# PCB-ACMb.net
KiCad netlist of a schematic drawn in EAGLE
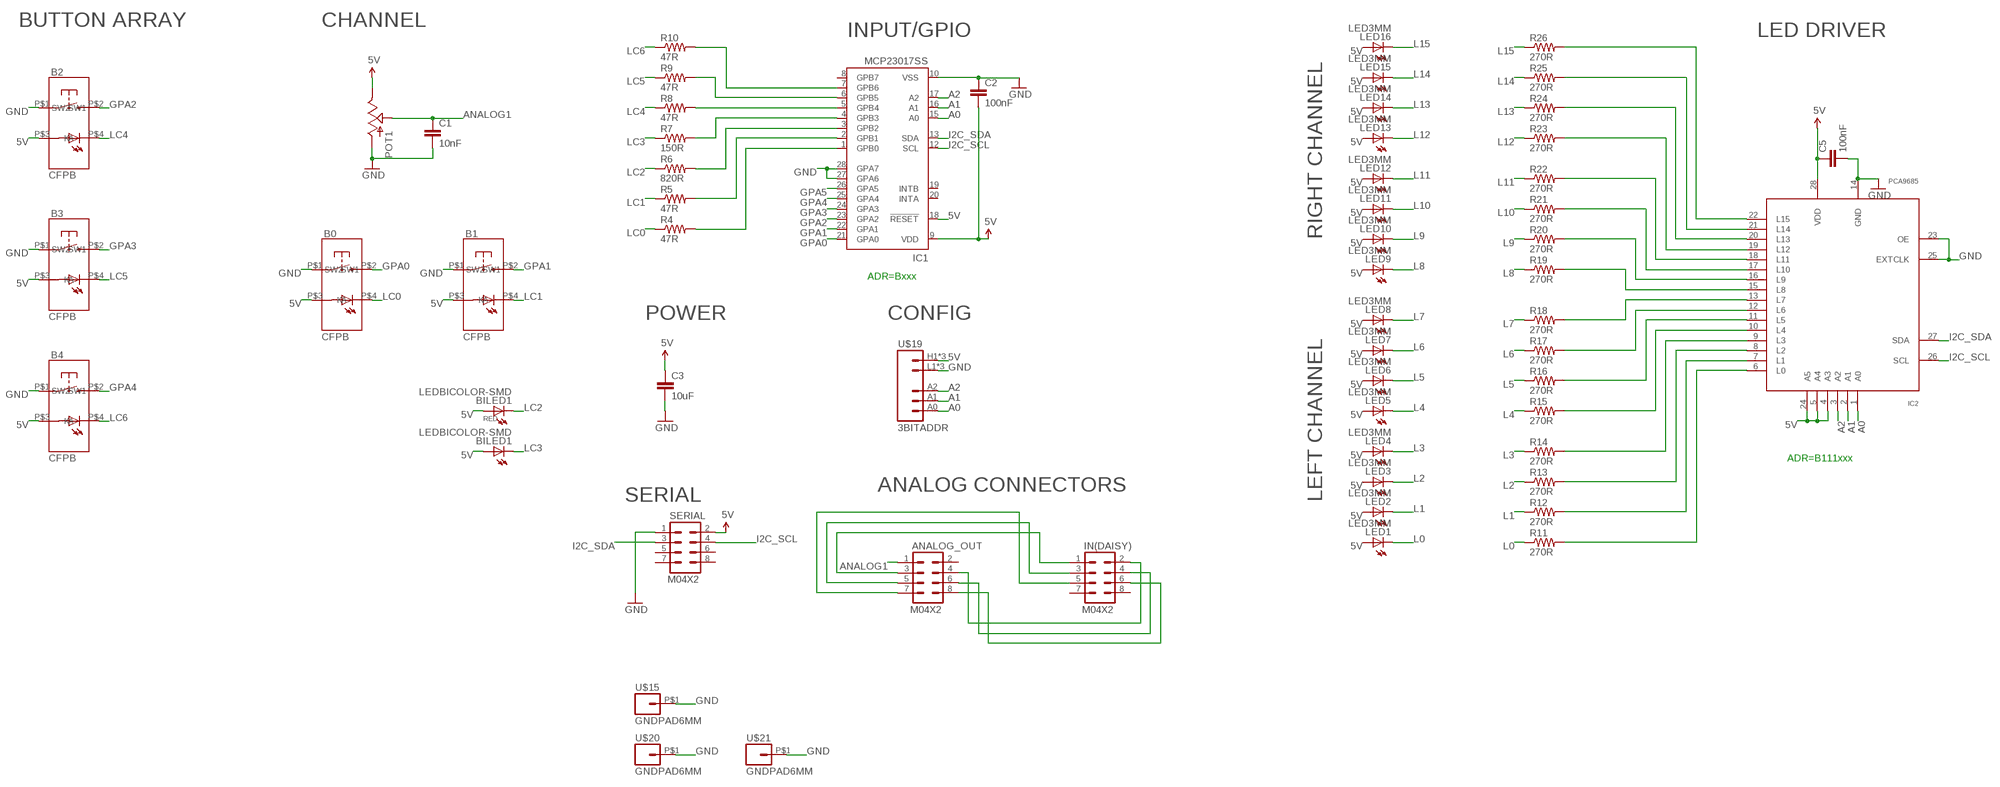
[diagram p0: schematic, sheet 1]

(export (version "E")
  (design (tool "Eeschema 10.0.6"))
  (components
    (comp (ref "ANALOG_OUT")
      (value "M04X2")
      (footprint "eagle-import:2X4")
      (libsource (lib "eagle-import") (part "M04X2"))
    )
    (comp (ref "B0")
      (value "CFPB")
      (footprint "eagle-import:CFPB-6_9MM")
      (libsource (lib "eagle-import") (part "CFPB"))
    )
    (comp (ref "B1")
      (value "CFPB")
      (footprint "eagle-import:CFPB-6_9MM")
      (libsource (lib "eagle-import") (part "CFPB"))
    )
    (comp (ref "B2")
      (value "CFPB")
      (footprint "eagle-import:CFPB-6_9MM")
      (libsource (lib "eagle-import") (part "CFPB"))
    )
    (comp (ref "B3")
      (value "CFPB")
      (footprint "eagle-import:CFPB-6_9MM")
      (libsource (lib "eagle-import") (part "CFPB"))
    )
    (comp (ref "B4")
      (value "CFPB")
      (footprint "eagle-import:CFPB-6_9MM")
      (libsource (lib "eagle-import") (part "CFPB"))
    )
    (comp (ref "BILED1")
      (value "LEDBICOLOR-SMD")
      (footprint "eagle-import:LEDBICOLOR-SMD")
      (libsource (lib "eagle-import") (part "LEDBICOLOR-SMD"))
    )
    (comp (ref "C1")
      (value "10nF")
      (footprint "eagle-import:0603-CAP")
      (libsource (lib "eagle-import") (part "CAP0603-CAP"))
    )
    (comp (ref "C2")
      (value "100nF")
      (footprint "eagle-import:0603-CAP")
      (libsource (lib "eagle-import") (part "CAP0603-CAP"))
    )
    (comp (ref "C3")
      (value "10uF")
      (footprint "eagle-import:0805")
      (libsource (lib "eagle-import") (part "CAP0805"))
    )
    (comp (ref "C5")
      (value "100nF")
      (footprint "eagle-import:0603-CAP")
      (libsource (lib "eagle-import") (part "CAP0603-CAP"))
    )
    (comp (ref "IC1")
      (value "MCP23017SS")
      (footprint "eagle-import:SSOP28")
      (fields
        (field (name "MF") "MICROCHIP")
        (field (name "MPN") "MCP23017-E/SS")
        (field (name "MPN_1") "MCP23017-E/SS")
        (field (name "OC_FARNELL") "1467674")
        (field (name "OC_NEWARK") "31K2960")
      )
      (libsource (lib "eagle-import") (part "MCP23017SS"))
    )
    (comp (ref "IC2")
      (value "PCA9685")
      (footprint "eagle-import:TSSOP28")
      (libsource (lib "eagle-import") (part "PCA9685"))
    )
    (comp (ref "IN(DAISY)")
      (value "M04X2")
      (footprint "eagle-import:2X4")
      (libsource (lib "eagle-import") (part "M04X2"))
    )
    (comp (ref "LED1")
      (value "LED3MM")
      (footprint "eagle-import:LED3MM")
      (libsource (lib "eagle-import") (part "LED3MM"))
    )
    (comp (ref "LED2")
      (value "LED3MM")
      (footprint "eagle-import:LED3MM")
      (libsource (lib "eagle-import") (part "LED3MM"))
    )
    (comp (ref "LED3")
      (value "LED3MM")
      (footprint "eagle-import:LED3MM")
      (libsource (lib "eagle-import") (part "LED3MM"))
    )
    (comp (ref "LED4")
      (value "LED3MM")
      (footprint "eagle-import:LED3MM")
      (libsource (lib "eagle-import") (part "LED3MM"))
    )
    (comp (ref "LED5")
      (value "LED3MM")
      (footprint "eagle-import:LED3MM")
      (libsource (lib "eagle-import") (part "LED3MM"))
    )
    (comp (ref "LED6")
      (value "LED3MM")
      (footprint "eagle-import:LED3MM")
      (libsource (lib "eagle-import") (part "LED3MM"))
    )
    (comp (ref "LED7")
      (value "LED3MM")
      (footprint "eagle-import:LED3MM")
      (libsource (lib "eagle-import") (part "LED3MM"))
    )
    (comp (ref "LED8")
      (value "LED3MM")
      (footprint "eagle-import:LED3MM")
      (libsource (lib "eagle-import") (part "LED3MM"))
    )
    (comp (ref "LED9")
      (value "LED3MM")
      (footprint "eagle-import:LED3MM")
      (libsource (lib "eagle-import") (part "LED3MM"))
    )
    (comp (ref "LED10")
      (value "LED3MM")
      (footprint "eagle-import:LED3MM")
      (libsource (lib "eagle-import") (part "LED3MM"))
    )
    (comp (ref "LED11")
      (value "LED3MM")
      (footprint "eagle-import:LED3MM")
      (libsource (lib "eagle-import") (part "LED3MM"))
    )
    (comp (ref "LED12")
      (value "LED3MM")
      (footprint "eagle-import:LED3MM")
      (libsource (lib "eagle-import") (part "LED3MM"))
    )
    (comp (ref "LED13")
      (value "LED3MM")
      (footprint "eagle-import:LED3MM")
      (libsource (lib "eagle-import") (part "LED3MM"))
    )
    (comp (ref "LED14")
      (value "LED3MM")
      (footprint "eagle-import:LED3MM")
      (libsource (lib "eagle-import") (part "LED3MM"))
    )
    (comp (ref "LED15")
      (value "LED3MM")
      (footprint "eagle-import:LED3MM")
      (libsource (lib "eagle-import") (part "LED3MM"))
    )
    (comp (ref "LED16")
      (value "LED3MM")
      (footprint "eagle-import:LED3MM")
      (libsource (lib "eagle-import") (part "LED3MM"))
    )
    (comp (ref "POT1")
      (value "POT")
      (footprint "eagle-import:ALPS_POT")
      (libsource (lib "eagle-import") (part "POT"))
    )
    (comp (ref "R4")
      (value "47R")
      (footprint "eagle-import:0603-RES")
      (libsource (lib "eagle-import") (part "RESISTOR0603-RES"))
    )
    (comp (ref "R5")
      (value "47R")
      (footprint "eagle-import:0603-RES")
      (libsource (lib "eagle-import") (part "RESISTOR0603-RES"))
    )
    (comp (ref "R6")
      (value "820R")
      (footprint "eagle-import:0603-RES")
      (libsource (lib "eagle-import") (part "RESISTOR0603-RES"))
    )
    (comp (ref "R7")
      (value "150R")
      (footprint "eagle-import:0603-RES")
      (libsource (lib "eagle-import") (part "RESISTOR0603-RES"))
    )
    (comp (ref "R8")
      (value "47R")
      (footprint "eagle-import:0603-RES")
      (libsource (lib "eagle-import") (part "RESISTOR0603-RES"))
    )
    (comp (ref "R9")
      (value "47R")
      (footprint "eagle-import:0603-RES")
      (libsource (lib "eagle-import") (part "RESISTOR0603-RES"))
    )
    (comp (ref "R10")
      (value "47R")
      (footprint "eagle-import:0603-RES")
      (libsource (lib "eagle-import") (part "RESISTOR0603-RES"))
    )
    (comp (ref "R11")
      (value "270R")
      (footprint "eagle-import:0603-RES")
      (libsource (lib "eagle-import") (part "RESISTOR0603-RES"))
    )
    (comp (ref "R12")
      (value "270R")
      (footprint "eagle-import:0603-RES")
      (libsource (lib "eagle-import") (part "RESISTOR0603-RES"))
    )
    (comp (ref "R13")
      (value "270R")
      (footprint "eagle-import:0603-RES")
      (libsource (lib "eagle-import") (part "RESISTOR0603-RES"))
    )
    (comp (ref "R14")
      (value "270R")
      (footprint "eagle-import:0603-RES")
      (libsource (lib "eagle-import") (part "RESISTOR0603-RES"))
    )
    (comp (ref "R15")
      (value "270R")
      (footprint "eagle-import:0603-RES")
      (libsource (lib "eagle-import") (part "RESISTOR0603-RES"))
    )
    (comp (ref "R16")
      (value "270R")
      (footprint "eagle-import:0603-RES")
      (libsource (lib "eagle-import") (part "RESISTOR0603-RES"))
    )
    (comp (ref "R17")
      (value "270R")
      (footprint "eagle-import:0603-RES")
      (libsource (lib "eagle-import") (part "RESISTOR0603-RES"))
    )
    (comp (ref "R18")
      (value "270R")
      (footprint "eagle-import:0603-RES")
      (libsource (lib "eagle-import") (part "RESISTOR0603-RES"))
    )
    (comp (ref "R19")
      (value "270R")
      (footprint "eagle-import:0603-RES")
      (libsource (lib "eagle-import") (part "RESISTOR0603-RES"))
    )
    (comp (ref "R20")
      (value "270R")
      (footprint "eagle-import:0603-RES")
      (libsource (lib "eagle-import") (part "RESISTOR0603-RES"))
    )
    (comp (ref "R21")
      (value "270R")
      (footprint "eagle-import:0603-RES")
      (libsource (lib "eagle-import") (part "RESISTOR0603-RES"))
    )
    (comp (ref "R22")
      (value "270R")
      (footprint "eagle-import:0603-RES")
      (libsource (lib "eagle-import") (part "RESISTOR0603-RES"))
    )
    (comp (ref "R23")
      (value "270R")
      (footprint "eagle-import:0603-RES")
      (libsource (lib "eagle-import") (part "RESISTOR0603-RES"))
    )
    (comp (ref "R24")
      (value "270R")
      (footprint "eagle-import:0603-RES")
      (libsource (lib "eagle-import") (part "RESISTOR0603-RES"))
    )
    (comp (ref "R25")
      (value "270R")
      (footprint "eagle-import:0603-RES")
      (libsource (lib "eagle-import") (part "RESISTOR0603-RES"))
    )
    (comp (ref "R26")
      (value "270R")
      (footprint "eagle-import:0603-RES")
      (libsource (lib "eagle-import") (part "RESISTOR0603-RES"))
    )
    (comp (ref "SERIAL")
      (value "M04X2")
      (footprint "eagle-import:2X4")
      (libsource (lib "eagle-import") (part "M04X2"))
    )
    (comp (ref "U$15")
      (value "GNDPAD6MM")
      (footprint "eagle-import:3.2MMPAD6MM")
      (libsource (lib "eagle-import") (part "GNDPAD6MM"))
    )
    (comp (ref "U$19")
      (value "3BITADDR")
      (footprint "eagle-import:3BITADDR")
      (libsource (lib "eagle-import") (part "3BITADDR"))
    )
    (comp (ref "U$20")
      (value "GNDPAD6MM")
      (footprint "eagle-import:3.2MMPAD6MM")
      (libsource (lib "eagle-import") (part "GNDPAD6MM"))
    )
    (comp (ref "U$21")
      (value "GNDPAD6MM")
      (footprint "eagle-import:3.2MMPAD6MM")
      (libsource (lib "eagle-import") (part "GNDPAD6MM"))
    )
  )
  (nets
    (net (code "1") (name "/A0") (class "Default")
      (node (ref "IC1") (pin "15") (pinfunction "A0_15") (pintype "input"))
      (node (ref "IC2") (pin "1") (pinfunction "A0_1") (pintype "input"))
      (node (ref "U$19") (pin "A0") (pinfunction "A0_A0") (pintype "passive"))
    )
    (net (code "2") (name "/A1") (class "Default")
      (node (ref "IC1") (pin "16") (pinfunction "A1_16") (pintype "input"))
      (node (ref "IC2") (pin "2") (pinfunction "A1_2") (pintype "input"))
      (node (ref "U$19") (pin "A1") (pinfunction "A1_A1") (pintype "passive"))
    )
    (net (code "3") (name "/A2") (class "Default")
      (node (ref "IC1") (pin "17") (pinfunction "A2_17") (pintype "input"))
      (node (ref "IC2") (pin "3") (pinfunction "A2_3") (pintype "input"))
      (node (ref "U$19") (pin "A2") (pinfunction "A2_A2") (pintype "passive"))
    )
    (net (code "4") (name "/ANALOG1") (class "Default")
      (node (ref "ANALOG_OUT") (pin "1") (pinfunction "1_1") (pintype "passive"))
      (node (ref "C1") (pin "1") (pinfunction "1_1") (pintype "passive"))
      (node (ref "POT1") (pin "P$2") (pinfunction "S_P$2") (pintype "passive"))
    )
    (net (code "5") (name "/GPA0") (class "Default")
      (node (ref "B0") (pin "P$2") (pinfunction "SW2_P$2") (pintype "bidirectional"))
      (node (ref "IC1") (pin "21") (pinfunction "GPA0_21") (pintype "bidirectional"))
    )
    (net (code "6") (name "/GPA1") (class "Default")
      (node (ref "B1") (pin "P$2") (pinfunction "SW2_P$2") (pintype "bidirectional"))
      (node (ref "IC1") (pin "22") (pinfunction "GPA1_22") (pintype "bidirectional"))
    )
    (net (code "7") (name "/GPA2") (class "Default")
      (node (ref "B2") (pin "P$2") (pinfunction "SW2_P$2") (pintype "bidirectional"))
      (node (ref "IC1") (pin "23") (pinfunction "GPA2_23") (pintype "bidirectional"))
    )
    (net (code "8") (name "/GPA3") (class "Default")
      (node (ref "B3") (pin "P$2") (pinfunction "SW2_P$2") (pintype "bidirectional"))
      (node (ref "IC1") (pin "24") (pinfunction "GPA3_24") (pintype "bidirectional"))
    )
    (net (code "9") (name "/GPA4") (class "Default")
      (node (ref "B4") (pin "P$2") (pinfunction "SW2_P$2") (pintype "bidirectional"))
      (node (ref "IC1") (pin "25") (pinfunction "GPA4_25") (pintype "bidirectional"))
    )
    (net (code "10") (name "/GPA5") (class "Default")
      (node (ref "IC1") (pin "26") (pinfunction "GPA5_26") (pintype "bidirectional"))
    )
    (net (code "11") (name "/I2C_SCL") (class "Default")
      (node (ref "IC1") (pin "12") (pinfunction "SCL_12") (pintype "input"))
      (node (ref "IC2") (pin "26") (pinfunction "SCL_26") (pintype "input"))
      (node (ref "SERIAL") (pin "4") (pinfunction "4_4") (pintype "passive"))
    )
    (net (code "12") (name "/I2C_SDA") (class "Default")
      (node (ref "IC1") (pin "13") (pinfunction "SDA_13") (pintype "bidirectional"))
      (node (ref "IC2") (pin "27") (pinfunction "SDA_27") (pintype "input"))
      (node (ref "SERIAL") (pin "3") (pinfunction "3_3") (pintype "passive"))
    )
    (net (code "13") (name "/L0") (class "Default")
      (node (ref "LED1") (pin "K") (pinfunction "C_K") (pintype "passive"))
      (node (ref "R11") (pin "1") (pinfunction "1_1") (pintype "passive"))
    )
    (net (code "14") (name "/L1") (class "Default")
      (node (ref "LED2") (pin "K") (pinfunction "C_K") (pintype "passive"))
      (node (ref "R12") (pin "1") (pinfunction "1_1") (pintype "passive"))
    )
    (net (code "15") (name "/L2") (class "Default")
      (node (ref "LED3") (pin "K") (pinfunction "C_K") (pintype "passive"))
      (node (ref "R13") (pin "1") (pinfunction "1_1") (pintype "passive"))
    )
    (net (code "16") (name "/L3") (class "Default")
      (node (ref "LED4") (pin "K") (pinfunction "C_K") (pintype "passive"))
      (node (ref "R14") (pin "1") (pinfunction "1_1") (pintype "passive"))
    )
    (net (code "17") (name "/L4") (class "Default")
      (node (ref "LED5") (pin "K") (pinfunction "C_K") (pintype "passive"))
      (node (ref "R15") (pin "1") (pinfunction "1_1") (pintype "passive"))
    )
    (net (code "18") (name "/L5") (class "Default")
      (node (ref "LED6") (pin "K") (pinfunction "C_K") (pintype "passive"))
      (node (ref "R16") (pin "1") (pinfunction "1_1") (pintype "passive"))
    )
    (net (code "19") (name "/L6") (class "Default")
      (node (ref "LED7") (pin "K") (pinfunction "C_K") (pintype "passive"))
      (node (ref "R17") (pin "1") (pinfunction "1_1") (pintype "passive"))
    )
    (net (code "20") (name "/L7") (class "Default")
      (node (ref "LED8") (pin "K") (pinfunction "C_K") (pintype "passive"))
      (node (ref "R18") (pin "1") (pinfunction "1_1") (pintype "passive"))
    )
    (net (code "21") (name "/L8") (class "Default")
      (node (ref "LED9") (pin "K") (pinfunction "C_K") (pintype "passive"))
      (node (ref "R19") (pin "1") (pinfunction "1_1") (pintype "passive"))
    )
    (net (code "22") (name "/L9") (class "Default")
      (node (ref "LED10") (pin "K") (pinfunction "C_K") (pintype "passive"))
      (node (ref "R20") (pin "1") (pinfunction "1_1") (pintype "passive"))
    )
    (net (code "23") (name "/L10") (class "Default")
      (node (ref "LED11") (pin "K") (pinfunction "C_K") (pintype "passive"))
      (node (ref "R21") (pin "1") (pinfunction "1_1") (pintype "passive"))
    )
    (net (code "24") (name "/L11") (class "Default")
      (node (ref "LED12") (pin "K") (pinfunction "C_K") (pintype "passive"))
      (node (ref "R22") (pin "1") (pinfunction "1_1") (pintype "passive"))
    )
    (net (code "25") (name "/L12") (class "Default")
      (node (ref "LED13") (pin "K") (pinfunction "C_K") (pintype "passive"))
      (node (ref "R23") (pin "1") (pinfunction "1_1") (pintype "passive"))
    )
    (net (code "26") (name "/L13") (class "Default")
      (node (ref "LED14") (pin "K") (pinfunction "C_K") (pintype "passive"))
      (node (ref "R24") (pin "1") (pinfunction "1_1") (pintype "passive"))
    )
    (net (code "27") (name "/L14") (class "Default")
      (node (ref "LED15") (pin "K") (pinfunction "C_K") (pintype "passive"))
      (node (ref "R25") (pin "1") (pinfunction "1_1") (pintype "passive"))
    )
    (net (code "28") (name "/L15") (class "Default")
      (node (ref "LED16") (pin "K") (pinfunction "C_K") (pintype "passive"))
      (node (ref "R26") (pin "1") (pinfunction "1_1") (pintype "passive"))
    )
    (net (code "29") (name "/LC0") (class "Default")
      (node (ref "B0") (pin "P$4") (pinfunction "K_P$4") (pintype "bidirectional"))
      (node (ref "R4") (pin "1") (pinfunction "1_1") (pintype "passive"))
    )
    (net (code "30") (name "/LC1") (class "Default")
      (node (ref "B1") (pin "P$4") (pinfunction "K_P$4") (pintype "bidirectional"))
      (node (ref "R5") (pin "1") (pinfunction "1_1") (pintype "passive"))
    )
    (net (code "31") (name "/LC2") (class "Default")
      (node (ref "BILED1") (pin "P$2") (pinfunction "C_P$2") (pintype "passive"))
      (node (ref "R6") (pin "1") (pinfunction "1_1") (pintype "passive"))
    )
    (net (code "32") (name "/LC3") (class "Default")
      (node (ref "BILED1") (pin "P$4") (pinfunction "C1_P$4") (pintype "passive"))
      (node (ref "R7") (pin "1") (pinfunction "1_1") (pintype "passive"))
    )
    (net (code "33") (name "/LC4") (class "Default")
      (node (ref "B2") (pin "P$4") (pinfunction "K_P$4") (pintype "bidirectional"))
      (node (ref "R8") (pin "1") (pinfunction "1_1") (pintype "passive"))
    )
    (net (code "34") (name "/LC5") (class "Default")
      (node (ref "B3") (pin "P$4") (pinfunction "K_P$4") (pintype "bidirectional"))
      (node (ref "R9") (pin "1") (pinfunction "1_1") (pintype "passive"))
    )
    (net (code "35") (name "/LC6") (class "Default")
      (node (ref "B4") (pin "P$4") (pinfunction "K_P$4") (pintype "bidirectional"))
      (node (ref "R10") (pin "1") (pinfunction "1_1") (pintype "passive"))
    )
    (net (code "36") (name "5V") (class "Default")
      (node (ref "B0") (pin "P$3") (pinfunction "A_P$3") (pintype "bidirectional"))
      (node (ref "B1") (pin "P$3") (pinfunction "A_P$3") (pintype "bidirectional"))
      (node (ref "B2") (pin "P$3") (pinfunction "A_P$3") (pintype "bidirectional"))
      (node (ref "B3") (pin "P$3") (pinfunction "A_P$3") (pintype "bidirectional"))
      (node (ref "B4") (pin "P$3") (pinfunction "A_P$3") (pintype "bidirectional"))
      (node (ref "BILED1") (pin "P$1") (pinfunction "A_P$1") (pintype "passive"))
      (node (ref "BILED1") (pin "P$3") (pinfunction "A1_P$3") (pintype "passive"))
      (node (ref "C2") (pin "2") (pinfunction "2_2") (pintype "passive"))
      (node (ref "C3") (pin "1") (pinfunction "1_1") (pintype "passive"))
      (node (ref "C5") (pin "1") (pinfunction "1_1") (pintype "passive"))
      (node (ref "IC1") (pin "18") (pinfunction "~{RESET}_18") (pintype "input"))
      (node (ref "IC1") (pin "9") (pinfunction "VDD_9") (pintype "power_in"))
      (node (ref "IC2") (pin "24") (pinfunction "A5_24") (pintype "input"))
      (node (ref "IC2") (pin "28") (pinfunction "VDD_28") (pintype "power_in"))
      (node (ref "IC2") (pin "4") (pinfunction "A3_4") (pintype "input"))
      (node (ref "IC2") (pin "5") (pinfunction "A4_5") (pintype "input"))
      (node (ref "LED1") (pin "A") (pinfunction "A_A") (pintype "passive"))
      (node (ref "LED10") (pin "A") (pinfunction "A_A") (pintype "passive"))
      (node (ref "LED11") (pin "A") (pinfunction "A_A") (pintype "passive"))
      (node (ref "LED12") (pin "A") (pinfunction "A_A") (pintype "passive"))
      (node (ref "LED13") (pin "A") (pinfunction "A_A") (pintype "passive"))
      (node (ref "LED14") (pin "A") (pinfunction "A_A") (pintype "passive"))
      (node (ref "LED15") (pin "A") (pinfunction "A_A") (pintype "passive"))
      (node (ref "LED16") (pin "A") (pinfunction "A_A") (pintype "passive"))
      (node (ref "LED2") (pin "A") (pinfunction "A_A") (pintype "passive"))
      (node (ref "LED3") (pin "A") (pinfunction "A_A") (pintype "passive"))
      (node (ref "LED4") (pin "A") (pinfunction "A_A") (pintype "passive"))
      (node (ref "LED5") (pin "A") (pinfunction "A_A") (pintype "passive"))
      (node (ref "LED6") (pin "A") (pinfunction "A_A") (pintype "passive"))
      (node (ref "LED7") (pin "A") (pinfunction "A_A") (pintype "passive"))
      (node (ref "LED8") (pin "A") (pinfunction "A_A") (pintype "passive"))
      (node (ref "LED9") (pin "A") (pinfunction "A_A") (pintype "passive"))
      (node (ref "POT1") (pin "P$1") (pinfunction "E_P$1") (pintype "passive"))
      (node (ref "SERIAL") (pin "2") (pinfunction "2_2") (pintype "passive"))
      (node (ref "U$19") (pin "H1") (pinfunction "VCC_H1") (pintype "passive"))
      (node (ref "U$19") (pin "H2") (pinfunction "VCC_H2") (pintype "passive"))
      (node (ref "U$19") (pin "H3") (pinfunction "VCC_H3") (pintype "passive"))
    )
    (net (code "37") (name "GND") (class "Default")
      (node (ref "B0") (pin "P$1") (pinfunction "SW1_P$1") (pintype "bidirectional"))
      (node (ref "B1") (pin "P$1") (pinfunction "SW1_P$1") (pintype "bidirectional"))
      (node (ref "B2") (pin "P$1") (pinfunction "SW1_P$1") (pintype "bidirectional"))
      (node (ref "B3") (pin "P$1") (pinfunction "SW1_P$1") (pintype "bidirectional"))
      (node (ref "B4") (pin "P$1") (pinfunction "SW1_P$1") (pintype "bidirectional"))
      (node (ref "C1") (pin "2") (pinfunction "2_2") (pintype "passive"))
      (node (ref "C2") (pin "1") (pinfunction "1_1") (pintype "passive"))
      (node (ref "C3") (pin "2") (pinfunction "2_2") (pintype "passive"))
      (node (ref "C5") (pin "2") (pinfunction "2_2") (pintype "passive"))
      (node (ref "IC1") (pin "10") (pinfunction "VSS_10") (pintype "power_in"))
      (node (ref "IC1") (pin "27") (pinfunction "GPA6_27") (pintype "bidirectional"))
      (node (ref "IC1") (pin "28") (pinfunction "GPA7_28") (pintype "bidirectional"))
      (node (ref "IC2") (pin "14") (pinfunction "GND_14") (pintype "power_in"))
      (node (ref "IC2") (pin "23") (pinfunction "OE_23") (pintype "input"))
      (node (ref "IC2") (pin "25") (pinfunction "EXTCLK_25") (pintype "input"))
      (node (ref "POT1") (pin "P$3") (pinfunction "A_P$3") (pintype "passive"))
      (node (ref "SERIAL") (pin "1") (pinfunction "1_1") (pintype "passive"))
      (node (ref "U$15") (pin "P$1") (pinfunction "1_P$1") (pintype "passive"))
      (node (ref "U$19") (pin "L1") (pinfunction "GND_L1") (pintype "passive"))
      (node (ref "U$19") (pin "L2") (pinfunction "GND_L2") (pintype "passive"))
      (node (ref "U$19") (pin "L3") (pinfunction "GND_L3") (pintype "passive"))
      (node (ref "U$20") (pin "P$1") (pinfunction "1_P$1") (pintype "passive"))
      (node (ref "U$21") (pin "P$1") (pinfunction "1_P$1") (pintype "passive"))
    )
    (net (code "38") (name "Net-(ANALOG_OUT-Pad3)") (class "Default")
      (node (ref "ANALOG_OUT") (pin "3") (pinfunction "3_3") (pintype "passive"))
      (node (ref "IN(DAISY)") (pin "1") (pinfunction "1_1") (pintype "passive"))
    )
    (net (code "39") (name "Net-(ANALOG_OUT-Pad4)") (class "Default")
      (node (ref "ANALOG_OUT") (pin "4") (pinfunction "4_4") (pintype "passive"))
      (node (ref "IN(DAISY)") (pin "2") (pinfunction "2_2") (pintype "passive"))
    )
    (net (code "40") (name "Net-(ANALOG_OUT-Pad5)") (class "Default")
      (node (ref "ANALOG_OUT") (pin "5") (pinfunction "5_5") (pintype "passive"))
      (node (ref "IN(DAISY)") (pin "3") (pinfunction "3_3") (pintype "passive"))
    )
    (net (code "41") (name "Net-(ANALOG_OUT-Pad6)") (class "Default")
      (node (ref "ANALOG_OUT") (pin "6") (pinfunction "6_6") (pintype "passive"))
      (node (ref "IN(DAISY)") (pin "4") (pinfunction "4_4") (pintype "passive"))
    )
    (net (code "42") (name "Net-(ANALOG_OUT-Pad7)") (class "Default")
      (node (ref "ANALOG_OUT") (pin "7") (pinfunction "7_7") (pintype "passive"))
      (node (ref "IN(DAISY)") (pin "5") (pinfunction "5_5") (pintype "passive"))
    )
    (net (code "43") (name "Net-(ANALOG_OUT-Pad8)") (class "Default")
      (node (ref "ANALOG_OUT") (pin "8") (pinfunction "8_8") (pintype "passive"))
      (node (ref "IN(DAISY)") (pin "6") (pinfunction "6_6") (pintype "passive"))
    )
    (net (code "44") (name "Net-(IC1-GPB0)") (class "Default")
      (node (ref "IC1") (pin "1") (pinfunction "GPB0_1") (pintype "bidirectional"))
      (node (ref "R4") (pin "2") (pinfunction "2_2") (pintype "passive"))
    )
    (net (code "45") (name "Net-(IC1-GPB1)") (class "Default")
      (node (ref "IC1") (pin "2") (pinfunction "GPB1_2") (pintype "bidirectional"))
      (node (ref "R5") (pin "2") (pinfunction "2_2") (pintype "passive"))
    )
    (net (code "46") (name "Net-(IC1-GPB2)") (class "Default")
      (node (ref "IC1") (pin "3") (pinfunction "GPB2_3") (pintype "bidirectional"))
      (node (ref "R6") (pin "2") (pinfunction "2_2") (pintype "passive"))
    )
    (net (code "47") (name "Net-(IC1-GPB3)") (class "Default")
      (node (ref "IC1") (pin "4") (pinfunction "GPB3_4") (pintype "bidirectional"))
      (node (ref "R7") (pin "2") (pinfunction "2_2") (pintype "passive"))
    )
    (net (code "48") (name "Net-(IC1-GPB4)") (class "Default")
      (node (ref "IC1") (pin "5") (pinfunction "GPB4_5") (pintype "bidirectional"))
      (node (ref "R8") (pin "2") (pinfunction "2_2") (pintype "passive"))
    )
    (net (code "49") (name "Net-(IC1-GPB5)") (class "Default")
      (node (ref "IC1") (pin "6") (pinfunction "GPB5_6") (pintype "bidirectional"))
      (node (ref "R9") (pin "2") (pinfunction "2_2") (pintype "passive"))
    )
    (net (code "50") (name "Net-(IC1-GPB6)") (class "Default")
      (node (ref "IC1") (pin "7") (pinfunction "GPB6_7") (pintype "bidirectional"))
      (node (ref "R10") (pin "2") (pinfunction "2_2") (pintype "passive"))
    )
    (net (code "51") (name "Net-(IC2-L0)") (class "Default")
      (node (ref "IC2") (pin "6") (pinfunction "L0_6") (pintype "output"))
      (node (ref "R11") (pin "2") (pinfunction "2_2") (pintype "passive"))
    )
    (net (code "52") (name "Net-(IC2-L1)") (class "Default")
      (node (ref "IC2") (pin "7") (pinfunction "L1_7") (pintype "output"))
      (node (ref "R12") (pin "2") (pinfunction "2_2") (pintype "passive"))
    )
    (net (code "53") (name "Net-(IC2-L2)") (class "Default")
      (node (ref "IC2") (pin "8") (pinfunction "L2_8") (pintype "output"))
      (node (ref "R13") (pin "2") (pinfunction "2_2") (pintype "passive"))
    )
    (net (code "54") (name "Net-(IC2-L3)") (class "Default")
      (node (ref "IC2") (pin "9") (pinfunction "L3_9") (pintype "output"))
      (node (ref "R14") (pin "2") (pinfunction "2_2") (pintype "passive"))
    )
    (net (code "55") (name "Net-(IC2-L4)") (class "Default")
      (node (ref "IC2") (pin "10") (pinfunction "L4_10") (pintype "output"))
      (node (ref "R15") (pin "2") (pinfunction "2_2") (pintype "passive"))
    )
    (net (code "56") (name "Net-(IC2-L5)") (class "Default")
      (node (ref "IC2") (pin "11") (pinfunction "L5_11") (pintype "output"))
      (node (ref "R16") (pin "2") (pinfunction "2_2") (pintype "passive"))
    )
    (net (code "57") (name "Net-(IC2-L6)") (class "Default")
      (node (ref "IC2") (pin "12") (pinfunction "L6_12") (pintype "output"))
      (node (ref "R17") (pin "2") (pinfunction "2_2") (pintype "passive"))
    )
    (net (code "58") (name "Net-(IC2-L7)") (class "Default")
      (node (ref "IC2") (pin "13") (pinfunction "L7_13") (pintype "output"))
      (node (ref "R18") (pin "2") (pinfunction "2_2") (pintype "passive"))
    )
    (net (code "59") (name "Net-(IC2-L8)") (class "Default")
      (node (ref "IC2") (pin "15") (pinfunction "L8_15") (pintype "output"))
      (node (ref "R19") (pin "2") (pinfunction "2_2") (pintype "passive"))
    )
    (net (code "60") (name "Net-(IC2-L9)") (class "Default")
      (node (ref "IC2") (pin "16") (pinfunction "L9_16") (pintype "output"))
      (node (ref "R20") (pin "2") (pinfunction "2_2") (pintype "passive"))
    )
    (net (code "61") (name "Net-(IC2-L10)") (class "Default")
      (node (ref "IC2") (pin "17") (pinfunction "L10_17") (pintype "output"))
      (node (ref "R21") (pin "2") (pinfunction "2_2") (pintype "passive"))
    )
    (net (code "62") (name "Net-(IC2-L11)") (class "Default")
      (node (ref "IC2") (pin "18") (pinfunction "L11_18") (pintype "output"))
      (node (ref "R22") (pin "2") (pinfunction "2_2") (pintype "passive"))
    )
    (net (code "63") (name "Net-(IC2-L12)") (class "Default")
      (node (ref "IC2") (pin "19") (pinfunction "L12_19") (pintype "output"))
      (node (ref "R23") (pin "2") (pinfunction "2_2") (pintype "passive"))
    )
    (net (code "64") (name "Net-(IC2-L13)") (class "Default")
      (node (ref "IC2") (pin "20") (pinfunction "L13_20") (pintype "output"))
      (node (ref "R24") (pin "2") (pinfunction "2_2") (pintype "passive"))
    )
    (net (code "65") (name "Net-(IC2-L14)") (class "Default")
      (node (ref "IC2") (pin "21") (pinfunction "L14_21") (pintype "output"))
      (node (ref "R25") (pin "2") (pinfunction "2_2") (pintype "passive"))
    )
    (net (code "66") (name "Net-(IC2-L15)") (class "Default")
      (node (ref "IC2") (pin "22") (pinfunction "L15_22") (pintype "output"))
      (node (ref "R26") (pin "2") (pinfunction "2_2") (pintype "passive"))
    )
    (net (code "67") (name "unconnected-(ANALOG_OUT-Pad2)") (class "Default")
      (node (ref "ANALOG_OUT") (pin "2") (pinfunction "2_2") (pintype "passive"))
    )
    (net (code "68") (name "unconnected-(IC1-GPB7-Pad8)") (class "Default")
      (node (ref "IC1") (pin "8") (pinfunction "GPB7_8") (pintype "bidirectional"))
    )
    (net (code "69") (name "unconnected-(IC1-INTA-Pad20)") (class "Default")
      (node (ref "IC1") (pin "20") (pinfunction "INTA_20") (pintype "output"))
    )
    (net (code "70") (name "unconnected-(IC1-INTB-Pad19)") (class "Default")
      (node (ref "IC1") (pin "19") (pinfunction "INTB_19") (pintype "output"))
    )
    (net (code "71") (name "unconnected-(IN(DAISY)-Pad7)") (class "Default")
      (node (ref "IN(DAISY)") (pin "7") (pinfunction "7_7") (pintype "passive"))
    )
    (net (code "72") (name "unconnected-(IN(DAISY)-Pad8)") (class "Default")
      (node (ref "IN(DAISY)") (pin "8") (pinfunction "8_8") (pintype "passive"))
    )
    (net (code "73") (name "unconnected-(SERIAL-Pad5)") (class "Default")
      (node (ref "SERIAL") (pin "5") (pinfunction "5_5") (pintype "passive"))
    )
    (net (code "74") (name "unconnected-(SERIAL-Pad6)") (class "Default")
      (node (ref "SERIAL") (pin "6") (pinfunction "6_6") (pintype "passive"))
    )
    (net (code "75") (name "unconnected-(SERIAL-Pad7)") (class "Default")
      (node (ref "SERIAL") (pin "7") (pinfunction "7_7") (pintype "passive"))
    )
    (net (code "76") (name "unconnected-(SERIAL-Pad8)") (class "Default")
      (node (ref "SERIAL") (pin "8") (pinfunction "8_8") (pintype "passive"))
    )
  )
)
